# Domino_JTAG_SPI.net
KiCad netlist of a schematic drawn in EAGLE
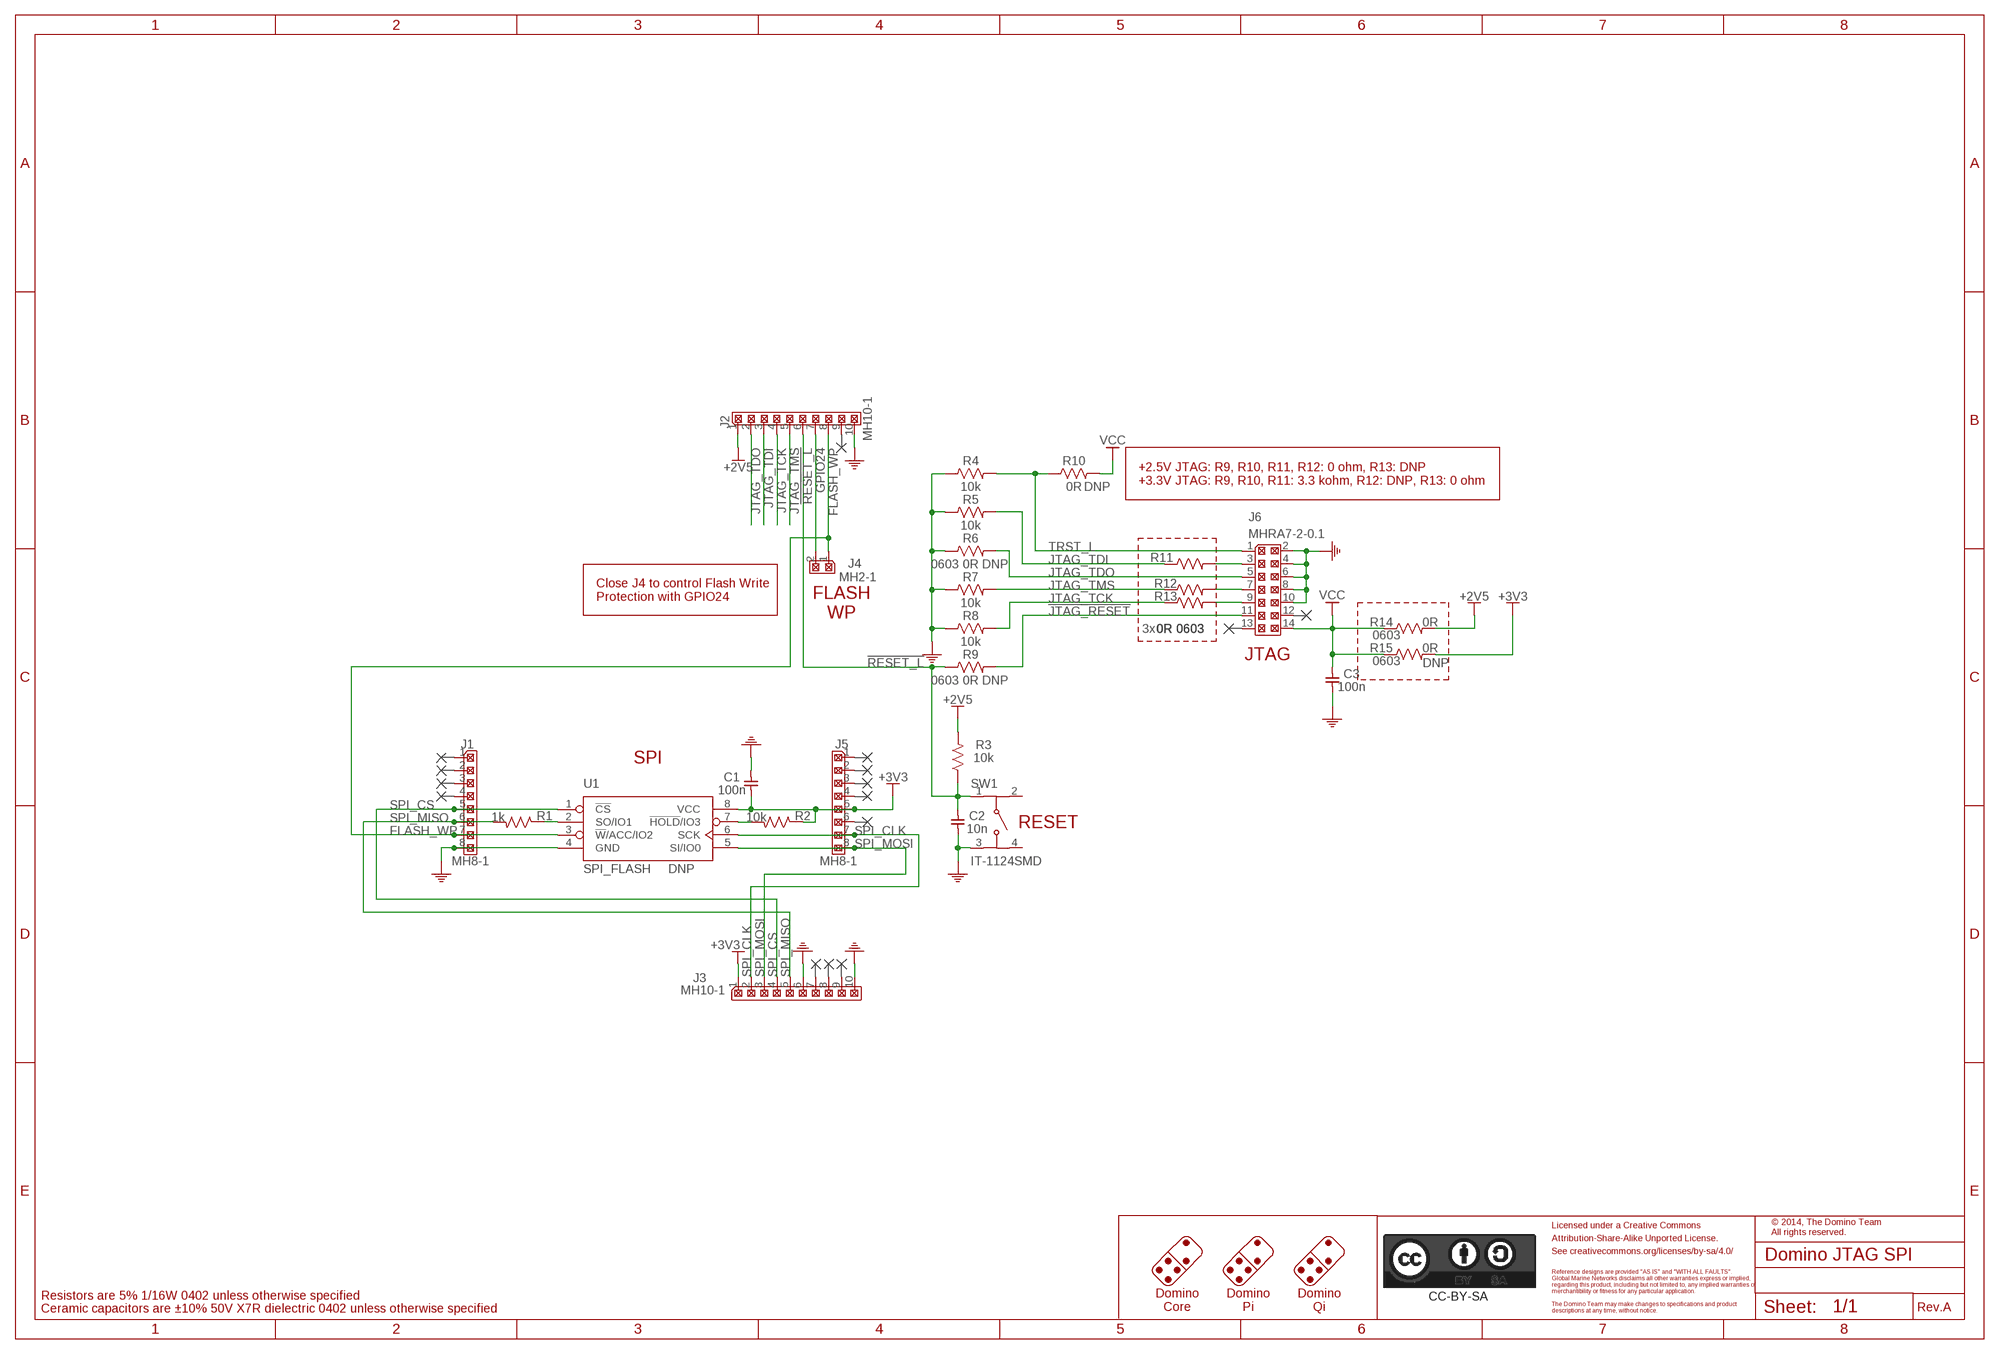
[diagram p0: schematic, sheet 1]

(export (version "E")
  (design (tool "Eeschema 10.0.6"))
  (components
    (comp (ref "C1")
      (value "100n")
      (footprint "eagle-import:C0402")
      (fields (field (name "PARTNO") "C0402_100n_X7R_10%_CER_50V"))
      (libsource (lib "eagle-import") (part "CAP_0402"))
    )
    (comp (ref "C2")
      (value "10n")
      (footprint "eagle-import:C0402")
      (fields (field (name "PARTNO") "C0402_10n_X7R_10%_CER_50V"))
      (libsource (lib "eagle-import") (part "CAP_0402"))
    )
    (comp (ref "C3")
      (value "100n")
      (footprint "eagle-import:C0402")
      (fields (field (name "PARTNO") "C0402_100n_X7R_10%_CER_50V"))
      (libsource (lib "eagle-import") (part "CAP_0402"))
    )
    (comp (ref "CC-BY-SA1")
      (value "CC-BY-SA_LOGO")
      (footprint "eagle-import:CC-BY-SA_LOGO")
      (libsource (lib "eagle-import") (part "CC-BY-SA_LOGO"))
    )
    (comp (ref "J1")
      (value "MH8-1")
      (footprint "eagle-import:MH8-1-0.1")
      (fields (field (name "PARTNO") "MH8-1-0.1"))
      (libsource (lib "eagle-import") (part "MH8-1"))
    )
    (comp (ref "J2")
      (value "MH10-1")
      (footprint "eagle-import:MH10-1-0.1")
      (fields (field (name "PARTNO") "MH10-1-0.1"))
      (libsource (lib "eagle-import") (part "MH10-1"))
    )
    (comp (ref "J3")
      (value "MH10-1")
      (footprint "eagle-import:MH10-1-0.1")
      (fields (field (name "PARTNO") "MH10-1-0.1"))
      (libsource (lib "eagle-import") (part "MH10-1"))
    )
    (comp (ref "J4")
      (value "MH2-1")
      (footprint "eagle-import:MH2-1-0.1")
      (fields (field (name "PARTNO") "MH2-1-0.1"))
      (libsource (lib "eagle-import") (part "MH2-1"))
    )
    (comp (ref "J5")
      (value "MH8-1")
      (footprint "eagle-import:MH8-1-0.1")
      (fields (field (name "PARTNO") "MH8-1-0.1"))
      (libsource (lib "eagle-import") (part "MH8-1"))
    )
    (comp (ref "J6")
      (value "MHRA7-2-0.1")
      (footprint "eagle-import:MHRA7-2-0.1")
      (libsource (lib "eagle-import") (part "MHRA7-2-0.1"))
    )
    (comp (ref "R1")
      (value "1k")
      (footprint "eagle-import:R0402")
      (fields (field (name "PARTNO") "R0402_1k_5%_62.5mW"))
      (libsource (lib "eagle-import") (part "RES_0402"))
    )
    (comp (ref "R2")
      (value "10k")
      (footprint "eagle-import:R0402")
      (fields (field (name "PARTNO") "R0402_10k_5%_62.5mW"))
      (libsource (lib "eagle-import") (part "RES_0402"))
    )
    (comp (ref "R3")
      (value "10k")
      (footprint "eagle-import:R0402")
      (fields (field (name "PARTNO") "R0402_10k_5%_62.5mW"))
      (libsource (lib "eagle-import") (part "RES_0402"))
    )
    (comp (ref "R4")
      (value "10k")
      (footprint "eagle-import:R0402")
      (fields (field (name "PARTNO") "R0402_10k_5%_62.5mW"))
      (libsource (lib "eagle-import") (part "RES_0402"))
    )
    (comp (ref "R5")
      (value "10k")
      (footprint "eagle-import:R0402")
      (fields (field (name "PARTNO") "R0402_10k_5%_62.5mW"))
      (libsource (lib "eagle-import") (part "RES_0402"))
    )
    (comp (ref "R6")
      (value "0R")
      (footprint "eagle-import:R0603")
      (fields (field (name "SIZE") "0603") (field (name "PARTNO") "R0603_0R_5%_125mW"))
      (libsource (lib "eagle-import") (part "RES_0603"))
    )
    (comp (ref "R7")
      (value "10k")
      (footprint "eagle-import:R0402")
      (fields (field (name "PARTNO") "R0402_10k_5%_62.5mW"))
      (libsource (lib "eagle-import") (part "RES_0402"))
    )
    (comp (ref "R8")
      (value "10k")
      (footprint "eagle-import:R0402")
      (fields (field (name "PARTNO") "R0402_10k_5%_62.5mW"))
      (libsource (lib "eagle-import") (part "RES_0402"))
    )
    (comp (ref "R9")
      (value "0R")
      (footprint "eagle-import:R0603")
      (fields (field (name "SIZE") "0603") (field (name "PARTNO") "R0603_0R_5%_125mW"))
      (libsource (lib "eagle-import") (part "RES_0603"))
    )
    (comp (ref "R10")
      (value "0R")
      (footprint "eagle-import:R0603")
      (fields (field (name "PARTNO") "R0603_0R_5%_125mW"))
      (libsource (lib "eagle-import") (part "RES_0603"))
    )
    (comp (ref "R11")
      (value "0R")
      (footprint "eagle-import:R0603")
      (fields (field (name "SIZE") "0603") (field (name "PARTNO") "R0603_0R_5%_125mW"))
      (libsource (lib "eagle-import") (part "RES_0603"))
    )
    (comp (ref "R12")
      (value "0R")
      (footprint "eagle-import:R0603")
      (fields (field (name "SIZE") "0603") (field (name "PARTNO") "R0603_0R_5%_125mW"))
      (libsource (lib "eagle-import") (part "RES_0603"))
    )
    (comp (ref "R13")
      (value "0R")
      (footprint "eagle-import:R0603")
      (fields (field (name "SIZE") "0603") (field (name "PARTNO") "R0603_0R_5%_125mW"))
      (libsource (lib "eagle-import") (part "RES_0603"))
    )
    (comp (ref "R14")
      (value "0R")
      (footprint "eagle-import:R0603")
      (fields (field (name "SIZE") "0603") (field (name "PARTNO") "R0603_0R_5%_125mW"))
      (libsource (lib "eagle-import") (part "RES_0603"))
    )
    (comp (ref "R15")
      (value "0R")
      (footprint "eagle-import:R0603")
      (fields (field (name "SIZE") "0603") (field (name "PARTNO") "R0603_0R_5%_125mW"))
      (libsource (lib "eagle-import") (part "RES_0603"))
    )
    (comp (ref "SW1")
      (value "IT-1124SMD")
      (footprint "eagle-import:IT-1124SMD")
      (libsource (lib "eagle-import") (part "IT-1124SMD"))
    )
    (comp (ref "U1")
      (value "SPI_FLASH")
      (footprint "eagle-import:SOIC-8")
      (libsource (lib "eagle-import") (part "SPI_FLASH"))
    )
  )
  (nets
    (net (code "1") (name "+2V5") (class "Default")
      (node (ref "J2") (pin "1") (pinfunction "1_1") (pintype "passive"))
      (node (ref "R14") (pin "2") (pinfunction "2_2") (pintype "passive"))
      (node (ref "R3") (pin "2") (pinfunction "2_2") (pintype "passive"))
    )
    (net (code "2") (name "+3V3") (class "Default")
      (node (ref "C1") (pin "2") (pinfunction "2_2") (pintype "passive"))
      (node (ref "J3") (pin "1") (pinfunction "1_1") (pintype "passive"))
      (node (ref "J5") (pin "5") (pinfunction "5_5") (pintype "passive"))
      (node (ref "R15") (pin "2") (pinfunction "2_2") (pintype "passive"))
      (node (ref "R2") (pin "1") (pinfunction "1_1") (pintype "passive"))
      (node (ref "U1") (pin "8") (pinfunction "VCC_8") (pintype "power_in"))
    )
    (net (code "3") (name "/FLASH_WP") (class "Default")
      (node (ref "J1") (pin "7") (pinfunction "7_7") (pintype "passive"))
      (node (ref "J2") (pin "8") (pinfunction "8_8") (pintype "passive"))
      (node (ref "J4") (pin "1") (pinfunction "1_1") (pintype "passive"))
      (node (ref "U1") (pin "3") (pinfunction "~{W}/ACC/IO2_3") (pintype "bidirectional"))
    )
    (net (code "4") (name "/GPIO24") (class "Default")
      (node (ref "J2") (pin "7") (pinfunction "7_7") (pintype "passive"))
      (node (ref "J4") (pin "2") (pinfunction "2_2") (pintype "passive"))
    )
    (net (code "5") (name "/JTAG_TCK") (class "Default")
      (node (ref "J2") (pin "4") (pinfunction "4_4") (pintype "passive"))
      (node (ref "R13") (pin "1") (pinfunction "1_1") (pintype "passive"))
      (node (ref "R8") (pin "2") (pinfunction "2_2") (pintype "passive"))
    )
    (net (code "6") (name "/JTAG_TDI") (class "Default")
      (node (ref "J2") (pin "3") (pinfunction "3_3") (pintype "passive"))
      (node (ref "R11") (pin "1") (pinfunction "1_1") (pintype "passive"))
      (node (ref "R5") (pin "2") (pinfunction "2_2") (pintype "passive"))
    )
    (net (code "7") (name "/JTAG_TDO") (class "Default")
      (node (ref "J2") (pin "2") (pinfunction "2_2") (pintype "passive"))
      (node (ref "J6") (pin "5") (pinfunction "5_5") (pintype "passive"))
      (node (ref "R6") (pin "2") (pinfunction "2_2") (pintype "passive"))
    )
    (net (code "8") (name "/JTAG_TMS") (class "Default")
      (node (ref "J2") (pin "5") (pinfunction "5_5") (pintype "passive"))
      (node (ref "R12") (pin "1") (pinfunction "1_1") (pintype "passive"))
      (node (ref "R7") (pin "2") (pinfunction "2_2") (pintype "passive"))
    )
    (net (code "9") (name "/SPI_CLK") (class "Default")
      (node (ref "J3") (pin "2") (pinfunction "2_2") (pintype "passive"))
      (node (ref "J5") (pin "7") (pinfunction "7_7") (pintype "passive"))
      (node (ref "U1") (pin "6") (pinfunction "SCK_6") (pintype "input"))
    )
    (net (code "10") (name "/SPI_CS") (class "Default")
      (node (ref "J1") (pin "5") (pinfunction "5_5") (pintype "passive"))
      (node (ref "J3") (pin "4") (pinfunction "4_4") (pintype "passive"))
      (node (ref "U1") (pin "1") (pinfunction "~{CS}_1") (pintype "input"))
    )
    (net (code "11") (name "/SPI_MISO") (class "Default")
      (node (ref "J1") (pin "6") (pinfunction "6_6") (pintype "passive"))
      (node (ref "J3") (pin "5") (pinfunction "5_5") (pintype "passive"))
      (node (ref "R1") (pin "2") (pinfunction "2_2") (pintype "passive"))
    )
    (net (code "12") (name "/SPI_MOSI") (class "Default")
      (node (ref "J3") (pin "3") (pinfunction "3_3") (pintype "passive"))
      (node (ref "J5") (pin "8") (pinfunction "8_8") (pintype "passive"))
      (node (ref "U1") (pin "5") (pinfunction "SI/IO0_5") (pintype "bidirectional"))
    )
    (net (code "13") (name "/TRST_L") (class "Default")
      (node (ref "J6") (pin "1") (pinfunction "1_1") (pintype "passive"))
      (node (ref "R10") (pin "1") (pinfunction "1_1") (pintype "passive"))
      (node (ref "R4") (pin "2") (pinfunction "2_2") (pintype "passive"))
    )
    (net (code "14") (name "/~{JTAG_RESET}") (class "Default")
      (node (ref "J6") (pin "11") (pinfunction "11_11") (pintype "passive"))
      (node (ref "R9") (pin "2") (pinfunction "2_2") (pintype "passive"))
    )
    (net (code "15") (name "/~{RESET_L}") (class "Default")
      (node (ref "C2") (pin "1") (pinfunction "1_1") (pintype "passive"))
      (node (ref "J2") (pin "6") (pinfunction "6_6") (pintype "passive"))
      (node (ref "R3") (pin "1") (pinfunction "1_1") (pintype "passive"))
      (node (ref "R9") (pin "1") (pinfunction "1_1") (pintype "passive"))
      (node (ref "SW1") (pin "1") (pinfunction "1_1") (pintype "passive"))
    )
    (net (code "16") (name "GND") (class "Default")
      (node (ref "C1") (pin "1") (pinfunction "1_1") (pintype "passive"))
      (node (ref "C2") (pin "2") (pinfunction "2_2") (pintype "passive"))
      (node (ref "C3") (pin "2") (pinfunction "2_2") (pintype "passive"))
      (node (ref "J1") (pin "8") (pinfunction "8_8") (pintype "passive"))
      (node (ref "J2") (pin "10") (pinfunction "10_10") (pintype "passive"))
      (node (ref "J3") (pin "10") (pinfunction "10_10") (pintype "passive"))
      (node (ref "J3") (pin "6") (pinfunction "6_6") (pintype "passive"))
      (node (ref "J6") (pin "10") (pinfunction "10_10") (pintype "passive"))
      (node (ref "J6") (pin "2") (pinfunction "2_2") (pintype "passive"))
      (node (ref "J6") (pin "4") (pinfunction "4_4") (pintype "passive"))
      (node (ref "J6") (pin "6") (pinfunction "6_6") (pintype "passive"))
      (node (ref "J6") (pin "8") (pinfunction "8_8") (pintype "passive"))
      (node (ref "R4") (pin "1") (pinfunction "1_1") (pintype "passive"))
      (node (ref "R5") (pin "1") (pinfunction "1_1") (pintype "passive"))
      (node (ref "R6") (pin "1") (pinfunction "1_1") (pintype "passive"))
      (node (ref "R7") (pin "1") (pinfunction "1_1") (pintype "passive"))
      (node (ref "R8") (pin "1") (pinfunction "1_1") (pintype "passive"))
      (node (ref "SW1") (pin "3") (pinfunction "3_3") (pintype "passive"))
      (node (ref "U1") (pin "4") (pinfunction "GND_4") (pintype "power_in"))
    )
    (net (code "17") (name "Net-(J6-Pad3)") (class "Default")
      (node (ref "J6") (pin "3") (pinfunction "3_3") (pintype "passive"))
      (node (ref "R11") (pin "2") (pinfunction "2_2") (pintype "passive"))
    )
    (net (code "18") (name "Net-(J6-Pad7)") (class "Default")
      (node (ref "J6") (pin "7") (pinfunction "7_7") (pintype "passive"))
      (node (ref "R12") (pin "2") (pinfunction "2_2") (pintype "passive"))
    )
    (net (code "19") (name "Net-(J6-Pad9)") (class "Default")
      (node (ref "J6") (pin "9") (pinfunction "9_9") (pintype "passive"))
      (node (ref "R13") (pin "2") (pinfunction "2_2") (pintype "passive"))
    )
    (net (code "20") (name "Net-(U1-SO{slash}IO1)") (class "Default")
      (node (ref "R1") (pin "1") (pinfunction "1_1") (pintype "passive"))
      (node (ref "U1") (pin "2") (pinfunction "SO/IO1_2") (pintype "bidirectional"))
    )
    (net (code "21") (name "Net-(U1-~{HOLD}{slash}IO3)") (class "Default")
      (node (ref "R2") (pin "2") (pinfunction "2_2") (pintype "passive"))
      (node (ref "U1") (pin "7") (pinfunction "~{HOLD}/IO3_7") (pintype "bidirectional"))
    )
    (net (code "22") (name "VCC") (class "Default")
      (node (ref "C3") (pin "1") (pinfunction "1_1") (pintype "passive"))
      (node (ref "J6") (pin "14") (pinfunction "14_14") (pintype "passive"))
      (node (ref "R10") (pin "2") (pinfunction "2_2") (pintype "passive"))
      (node (ref "R14") (pin "1") (pinfunction "1_1") (pintype "passive"))
      (node (ref "R15") (pin "1") (pinfunction "1_1") (pintype "passive"))
    )
    (net (code "23") (name "unconnected-(J1-Pad1)") (class "Default")
      (node (ref "J1") (pin "1") (pinfunction "1_1") (pintype "passive"))
    )
    (net (code "24") (name "unconnected-(J1-Pad2)") (class "Default")
      (node (ref "J1") (pin "2") (pinfunction "2_2") (pintype "passive"))
    )
    (net (code "25") (name "unconnected-(J1-Pad3)") (class "Default")
      (node (ref "J1") (pin "3") (pinfunction "3_3") (pintype "passive"))
    )
    (net (code "26") (name "unconnected-(J1-Pad4)") (class "Default")
      (node (ref "J1") (pin "4") (pinfunction "4_4") (pintype "passive"))
    )
    (net (code "27") (name "unconnected-(J2-Pad9)") (class "Default")
      (node (ref "J2") (pin "9") (pinfunction "9_9") (pintype "passive"))
    )
    (net (code "28") (name "unconnected-(J3-Pad7)") (class "Default")
      (node (ref "J3") (pin "7") (pinfunction "7_7") (pintype "passive"))
    )
    (net (code "29") (name "unconnected-(J3-Pad8)") (class "Default")
      (node (ref "J3") (pin "8") (pinfunction "8_8") (pintype "passive"))
    )
    (net (code "30") (name "unconnected-(J3-Pad9)") (class "Default")
      (node (ref "J3") (pin "9") (pinfunction "9_9") (pintype "passive"))
    )
    (net (code "31") (name "unconnected-(J5-Pad1)") (class "Default")
      (node (ref "J5") (pin "1") (pinfunction "1_1") (pintype "passive"))
    )
    (net (code "32") (name "unconnected-(J5-Pad2)") (class "Default")
      (node (ref "J5") (pin "2") (pinfunction "2_2") (pintype "passive"))
    )
    (net (code "33") (name "unconnected-(J5-Pad3)") (class "Default")
      (node (ref "J5") (pin "3") (pinfunction "3_3") (pintype "passive"))
    )
    (net (code "34") (name "unconnected-(J5-Pad4)") (class "Default")
      (node (ref "J5") (pin "4") (pinfunction "4_4") (pintype "passive"))
    )
    (net (code "35") (name "unconnected-(J5-Pad6)") (class "Default")
      (node (ref "J5") (pin "6") (pinfunction "6_6") (pintype "passive"))
    )
    (net (code "36") (name "unconnected-(J6-Pad12)") (class "Default")
      (node (ref "J6") (pin "12") (pinfunction "12_12") (pintype "passive"))
    )
    (net (code "37") (name "unconnected-(J6-Pad13)") (class "Default")
      (node (ref "J6") (pin "13") (pinfunction "13_13") (pintype "passive"))
    )
    (net (code "38") (name "unconnected-(SW1-Pad2)") (class "Default")
      (node (ref "SW1") (pin "2") (pinfunction "2_2") (pintype "passive"))
    )
    (net (code "39") (name "unconnected-(SW1-Pad4)") (class "Default")
      (node (ref "SW1") (pin "4") (pinfunction "4_4") (pintype "passive"))
    )
  )
)
